# MCUSTM32F4ZGT6.net
KiCad netlist of a schematic drawn in Altium Designer
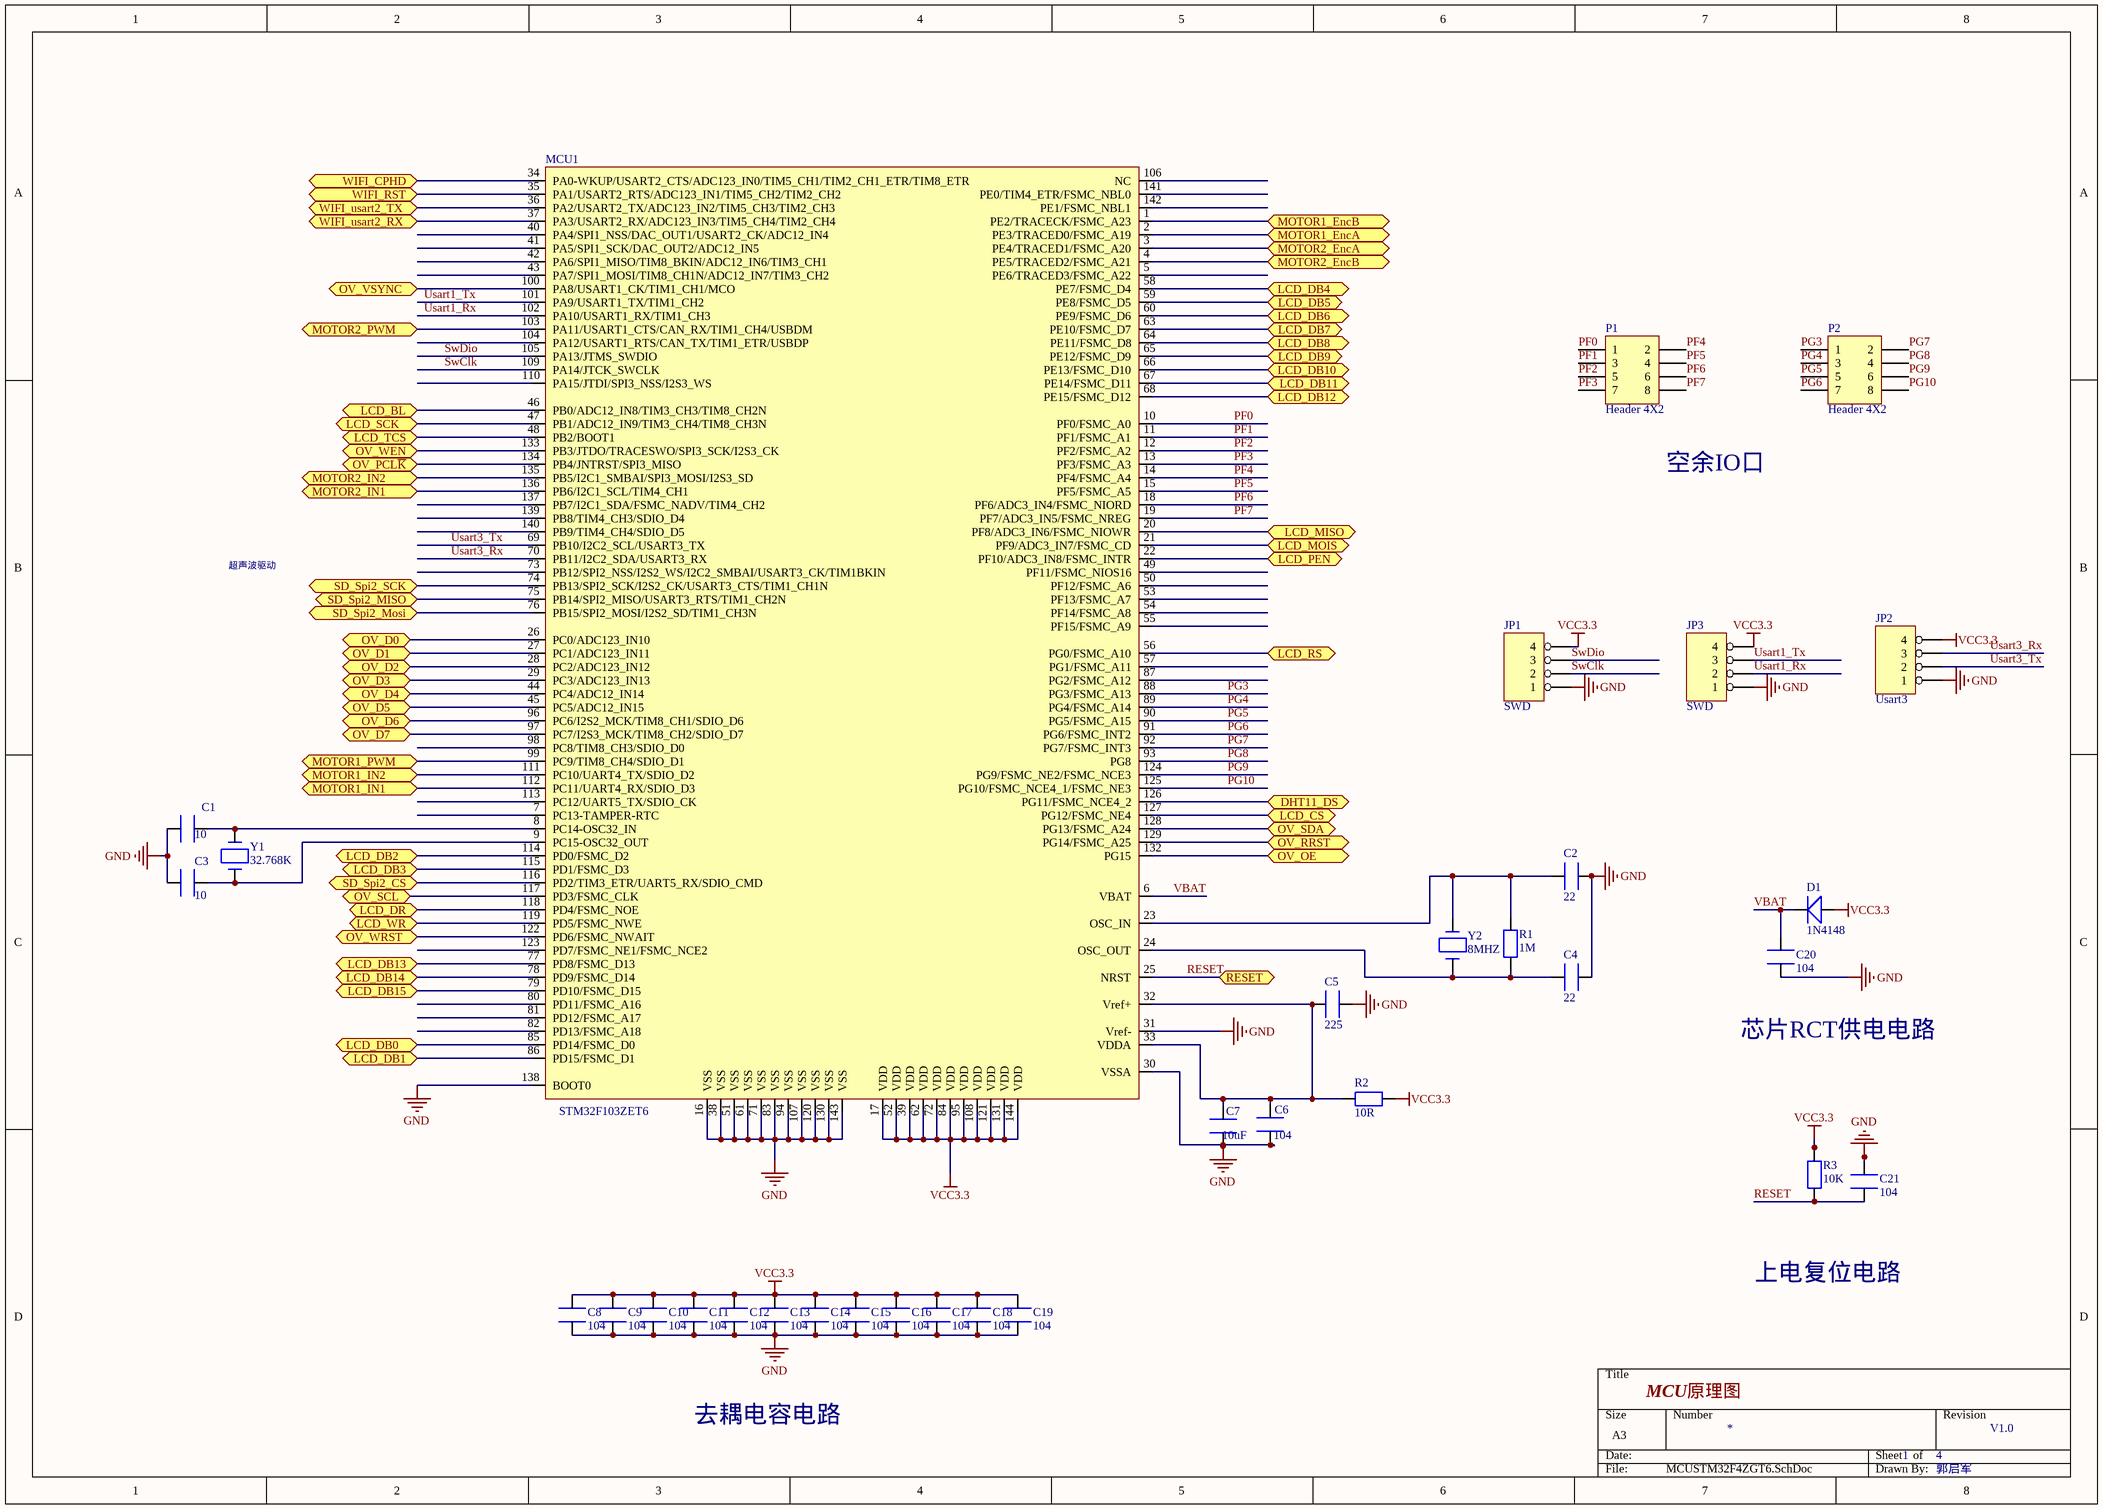
[diagram p0: MCUSTM32F4ZGT6.SchDoc]

(export (version "E")
  (design (tool "Eeschema 10.0.6"))
  (components
    (comp (ref "C1")
      (value "10")
      (footprint "0805-bottom layer")
      (description "电容")
      (libsource (lib "Baymax") (part "10"))
    )
    (comp (ref "C2")
      (value "22")
      (footprint "0805-bottom layer")
      (description "电容")
      (libsource (lib "Baymax") (part "22"))
    )
    (comp (ref "C3")
      (value "10")
      (footprint "0805-bottom layer")
      (description "电容")
      (libsource (lib "Baymax") (part "10"))
    )
    (comp (ref "C4")
      (value "22")
      (footprint "0805-bottom layer")
      (description "电容")
      (libsource (lib "Baymax") (part "22"))
    )
    (comp (ref "C5")
      (value "225")
      (footprint "0805-bottom layer")
      (description "电容")
      (libsource (lib "Baymax") (part "225"))
    )
    (comp (ref "C6")
      (value "104")
      (footprint "0805-bottom layer")
      (description "电容")
      (libsource (lib "Baymax") (part "104"))
    )
    (comp (ref "C7")
      (value "10uF")
      (footprint "0805-bottom layer")
      (description "电容")
      (libsource (lib "Baymax") (part "10uF"))
    )
    (comp (ref "C8")
      (value "104")
      (footprint "0805-bottom layer")
      (description "电容")
      (libsource (lib "Baymax") (part "104"))
    )
    (comp (ref "C9")
      (value "104")
      (footprint "0805-bottom layer")
      (description "电容")
      (libsource (lib "Baymax") (part "104"))
    )
    (comp (ref "C10")
      (value "104")
      (footprint "0805-bottom layer")
      (description "电容")
      (libsource (lib "Baymax") (part "104"))
    )
    (comp (ref "C11")
      (value "104")
      (footprint "0805-bottom layer")
      (description "电容")
      (libsource (lib "Baymax") (part "104"))
    )
    (comp (ref "C12")
      (value "104")
      (footprint "0805-bottom layer")
      (description "电容")
      (libsource (lib "Baymax") (part "104"))
    )
    (comp (ref "C13")
      (value "104")
      (footprint "0805-bottom layer")
      (description "电容")
      (libsource (lib "Baymax") (part "104"))
    )
    (comp (ref "C14")
      (value "104")
      (footprint "0805-bottom layer")
      (description "电容")
      (libsource (lib "Baymax") (part "104"))
    )
    (comp (ref "C15")
      (value "104")
      (footprint "0805-bottom layer")
      (description "电容")
      (libsource (lib "Baymax") (part "104"))
    )
    (comp (ref "C16")
      (value "104")
      (footprint "0805-bottom layer")
      (description "电容")
      (libsource (lib "Baymax") (part "104"))
    )
    (comp (ref "C17")
      (value "104")
      (footprint "0805-bottom layer")
      (description "电容")
      (libsource (lib "Baymax") (part "104"))
    )
    (comp (ref "C18")
      (value "104")
      (footprint "0805-bottom layer")
      (description "电容")
      (libsource (lib "Baymax") (part "104"))
    )
    (comp (ref "C19")
      (value "104")
      (footprint "0805-bottom layer")
      (description "电容")
      (libsource (lib "Baymax") (part "104"))
    )
    (comp (ref "C20")
      (value "104")
      (footprint "0805-bottom layer")
      (description "电容")
      (libsource (lib "Baymax") (part "104"))
    )
    (comp (ref "C21")
      (value "104")
      (footprint "0805-bottom layer")
      (description "电容")
      (libsource (lib "Baymax") (part "104"))
    )
    (comp (ref "D1")
      (value "1N4148")
      (footprint "DIODE_SOP")
      (description "限流二极管")
      (libsource (lib "Baymax") (part "1N4148"))
    )
    (comp (ref "JP1")
      (value "SWD")
      (footprint "HDR1X4")
      (libsource (lib "Connector Class") (part "HEADER 4"))
    )
    (comp (ref "JP2")
      (value "Usart3")
      (footprint "HDR1X4")
      (libsource (lib "Connector Class") (part "HEADER 4"))
    )
    (comp (ref "JP3") (value "SWD") (footprint "HDR1X4") (libsource (lib "BAYMAX_") (part "HEADER 4")))
    (comp (ref "MCU1")
      (value "STM32F103ZET6")
      (footprint "LQFP144")
      (libsource (lib "Baymax") (part "STM32F103ZET6"))
    )
    (comp (ref "P1")
      (value "Header 4X2")
      (footprint "HDR2X4")
      (description "Header, 4-Pin, Dual row")
      (fields (field (name "PUBLISHER") "Altium Limited"))
      (libsource (lib "Miscellaneous Connectors") (part "Header 4X2"))
    )
    (comp (ref "P2")
      (value "Header 4X2")
      (footprint "HDR2X4")
      (description "Header, 4-Pin, Dual row")
      (fields (field (name "PUBLISHER") "Altium Limited"))
      (libsource (lib "Miscellaneous Connectors") (part "Header 4X2"))
    )
    (comp (ref "R1")
      (value "1M")
      (footprint "0805-bottom layer")
      (description "电阻")
      (libsource (lib "Baymax") (part "1M"))
    )
    (comp (ref "R2")
      (value "10R")
      (footprint "0805-bottom layer")
      (description "电阻")
      (libsource (lib "Baymax") (part "10R"))
    )
    (comp (ref "R3")
      (value "10K")
      (footprint "0805-bottom layer")
      (description "电阻")
      (libsource (lib "Baymax") (part "10K"))
    )
    (comp (ref "Y1")
      (value "32.768K")
      (footprint "XTAL32")
      (description "晶振")
      (libsource (lib "Baymax") (part "32.768K"))
    )
    (comp (ref "Y2")
      (value "8MHZ")
      (footprint "XTAL_US")
      (description "晶振")
      (libsource (lib "Baymax") (part "8MHZ"))
    )
  )
  (nets
    (net (code "1") (name "/DHT11_DS") (class "Default")
      (node (ref "MCU1") (pin "126") (pinfunction "PG11/FSMC_NCE4_2_126") (pintype "passive"))
    )
    (net (code "2") (name "/LCD_BL") (class "Default")
      (node (ref "MCU1") (pin "46") (pinfunction "PB0/ADC12_IN8/TIM3_CH3/TIM8_CH2N_46") (pintype "passive"))
    )
    (net (code "3") (name "/LCD_CS") (class "Default")
      (node (ref "MCU1") (pin "127") (pinfunction "PG12/FSMC_NE4_127") (pintype "passive"))
    )
    (net (code "4") (name "/LCD_DB0") (class "Default")
      (node (ref "MCU1") (pin "85") (pinfunction "PD14/FSMC_D0_85") (pintype "passive"))
    )
    (net (code "5") (name "/LCD_DB1") (class "Default")
      (node (ref "MCU1") (pin "86") (pinfunction "PD15/FSMC_D1_86") (pintype "passive"))
    )
    (net (code "6") (name "/LCD_DB2") (class "Default")
      (node (ref "MCU1") (pin "114") (pinfunction "PD0/FSMC_D2_114") (pintype "passive"))
    )
    (net (code "7") (name "/LCD_DB3") (class "Default")
      (node (ref "MCU1") (pin "115") (pinfunction "PD1/FSMC_D3_115") (pintype "passive"))
    )
    (net (code "8") (name "/LCD_DB4") (class "Default")
      (node (ref "MCU1") (pin "58") (pinfunction "PE7/FSMC_D4_58") (pintype "passive"))
    )
    (net (code "9") (name "/LCD_DB5") (class "Default")
      (node (ref "MCU1") (pin "59") (pinfunction "PE8/FSMC_D5_59") (pintype "passive"))
    )
    (net (code "10") (name "/LCD_DB6") (class "Default")
      (node (ref "MCU1") (pin "60") (pinfunction "PE9/FSMC_D6_60") (pintype "passive"))
    )
    (net (code "11") (name "/LCD_DB7") (class "Default")
      (node (ref "MCU1") (pin "63") (pinfunction "PE10/FSMC_D7_63") (pintype "passive"))
    )
    (net (code "12") (name "/LCD_DB8") (class "Default")
      (node (ref "MCU1") (pin "64") (pinfunction "PE11/FSMC_D8_64") (pintype "passive"))
    )
    (net (code "13") (name "/LCD_DB9") (class "Default")
      (node (ref "MCU1") (pin "65") (pinfunction "PE12/FSMC_D9_65") (pintype "passive"))
    )
    (net (code "14") (name "/LCD_DB10") (class "Default")
      (node (ref "MCU1") (pin "66") (pinfunction "PE13/FSMC_D10_66") (pintype "passive"))
    )
    (net (code "15") (name "/LCD_DB11") (class "Default")
      (node (ref "MCU1") (pin "67") (pinfunction "PE14/FSMC_D11_67") (pintype "passive"))
    )
    (net (code "16") (name "/LCD_DB12") (class "Default")
      (node (ref "MCU1") (pin "68") (pinfunction "PE15/FSMC_D12_68") (pintype "passive"))
    )
    (net (code "17") (name "/LCD_DB13") (class "Default")
      (node (ref "MCU1") (pin "77") (pinfunction "PD8/FSMC_D13_77") (pintype "passive"))
    )
    (net (code "18") (name "/LCD_DB14") (class "Default")
      (node (ref "MCU1") (pin "78") (pinfunction "PD9/FSMC_D14_78") (pintype "passive"))
    )
    (net (code "19") (name "/LCD_DB15") (class "Default")
      (node (ref "MCU1") (pin "79") (pinfunction "PD10/FSMC_D15_79") (pintype "passive"))
    )
    (net (code "20") (name "/LCD_DR") (class "Default")
      (node (ref "MCU1") (pin "118") (pinfunction "PD4/FSMC_NOE_118") (pintype "passive"))
    )
    (net (code "21") (name "/LCD_MISO") (class "Default")
      (node (ref "MCU1") (pin "20") (pinfunction "PF8/ADC3_IN6/FSMC_NIOWR_20") (pintype "passive"))
    )
    (net (code "22") (name "/LCD_MOIS") (class "Default")
      (node (ref "MCU1") (pin "21") (pinfunction "PF9/ADC3_IN7/FSMC_CD_21") (pintype "passive"))
    )
    (net (code "23") (name "/LCD_PEN") (class "Default")
      (node (ref "MCU1") (pin "22") (pinfunction "PF10/ADC3_IN8/FSMC_INTR_22") (pintype "passive"))
    )
    (net (code "24") (name "/LCD_RS") (class "Default")
      (node (ref "MCU1") (pin "56") (pinfunction "PG0/FSMC_A10_56") (pintype "passive"))
    )
    (net (code "25") (name "/LCD_SCK") (class "Default")
      (node (ref "MCU1") (pin "47") (pinfunction "PB1/ADC12_IN9/TIM3_CH4/TIM8_CH3N_47") (pintype "passive"))
    )
    (net (code "26") (name "/LCD_TCS") (class "Default")
      (node (ref "MCU1") (pin "48") (pinfunction "PB2/BOOT1_48") (pintype "passive"))
    )
    (net (code "27") (name "/LCD_WR") (class "Default")
      (node (ref "MCU1") (pin "119") (pinfunction "PD5/FSMC_NWE_119") (pintype "passive"))
    )
    (net (code "28") (name "/MOTOR1_EncA") (class "Default")
      (node (ref "MCU1") (pin "2") (pinfunction "PE3/TRACED0/FSMC_A19_2") (pintype "passive"))
    )
    (net (code "29") (name "/MOTOR1_EncB") (class "Default")
      (node (ref "MCU1") (pin "1") (pinfunction "PE2/TRACECK/FSMC_A23_1") (pintype "passive"))
    )
    (net (code "30") (name "/MOTOR1_IN1") (class "Default")
      (node (ref "MCU1") (pin "112") (pinfunction "PC11/UART4_RX/SDIO_D3_112") (pintype "passive"))
    )
    (net (code "31") (name "/MOTOR1_IN2") (class "Default")
      (node (ref "MCU1") (pin "111") (pinfunction "PC10/UART4_TX/SDIO_D2_111") (pintype "passive"))
    )
    (net (code "32") (name "/MOTOR1_PWM") (class "Default")
      (node (ref "MCU1") (pin "99") (pinfunction "PC9/TIM8_CH4/SDIO_D1_99") (pintype "passive"))
    )
    (net (code "33") (name "/MOTOR2_EncA") (class "Default")
      (node (ref "MCU1") (pin "3") (pinfunction "PE4/TRACED1/FSMC_A20_3") (pintype "passive"))
    )
    (net (code "34") (name "/MOTOR2_EncB") (class "Default")
      (node (ref "MCU1") (pin "4") (pinfunction "PE5/TRACED2/FSMC_A21_4") (pintype "passive"))
    )
    (net (code "35") (name "/MOTOR2_IN1") (class "Default")
      (node (ref "MCU1") (pin "136") (pinfunction "PB6/I2C1_SCL/TIM4_CH1_136") (pintype "passive"))
    )
    (net (code "36") (name "/MOTOR2_IN2") (class "Default")
      (node (ref "MCU1") (pin "135") (pinfunction "PB5/I2C1_SMBAI/SPI3_MOSI/I2S3_SD_135") (pintype "passive"))
    )
    (net (code "37") (name "/MOTOR2_PWM") (class "Default")
      (node (ref "MCU1") (pin "103") (pinfunction "PA11/USART1_CTS/CAN_RX/TIM1_CH4/USBDM_103") (pintype "passive"))
    )
    (net (code "38") (name "/OV_D0") (class "Default")
      (node (ref "MCU1") (pin "26") (pinfunction "PC0/ADC123_IN10_26") (pintype "passive"))
    )
    (net (code "39") (name "/OV_D1") (class "Default")
      (node (ref "MCU1") (pin "27") (pinfunction "PC1/ADC123_IN11_27") (pintype "passive"))
    )
    (net (code "40") (name "/OV_D2") (class "Default")
      (node (ref "MCU1") (pin "28") (pinfunction "PC2/ADC123_IN12_28") (pintype "passive"))
    )
    (net (code "41") (name "/OV_D3") (class "Default")
      (node (ref "MCU1") (pin "29") (pinfunction "PC3/ADC123_IN13_29") (pintype "passive"))
    )
    (net (code "42") (name "/OV_D4") (class "Default")
      (node (ref "MCU1") (pin "44") (pinfunction "PC4/ADC12_IN14_44") (pintype "passive"))
    )
    (net (code "43") (name "/OV_D5") (class "Default")
      (node (ref "MCU1") (pin "45") (pinfunction "PC5/ADC12_IN15_45") (pintype "passive"))
    )
    (net (code "44") (name "/OV_D6") (class "Default")
      (node (ref "MCU1") (pin "96") (pinfunction "PC6/I2S2_MCK/TIM8_CH1/SDIO_D6_96") (pintype "passive"))
    )
    (net (code "45") (name "/OV_D7") (class "Default")
      (node (ref "MCU1") (pin "97") (pinfunction "PC7/I2S3_MCK/TIM8_CH2/SDIO_D7_97") (pintype "passive"))
    )
    (net (code "46") (name "/OV_OE") (class "Default")
      (node (ref "MCU1") (pin "132") (pinfunction "PG15_132") (pintype "passive"))
    )
    (net (code "47") (name "/OV_PCL~{K}") (class "Default")
      (node (ref "MCU1") (pin "134") (pinfunction "PB4/JNTRST/SPI3_MISO_134") (pintype "passive"))
    )
    (net (code "48") (name "/OV_RRST") (class "Default")
      (node (ref "MCU1") (pin "129") (pinfunction "PG14/FSMC_A25_129") (pintype "passive"))
    )
    (net (code "49") (name "/OV_SCL") (class "Default")
      (node (ref "MCU1") (pin "117") (pinfunction "PD3/FSMC_CLK_117") (pintype "passive"))
    )
    (net (code "50") (name "/OV_SDA") (class "Default")
      (node (ref "MCU1") (pin "128") (pinfunction "PG13/FSMC_A24_128") (pintype "passive"))
    )
    (net (code "51") (name "/OV_VSYNC") (class "Default")
      (node (ref "MCU1") (pin "100") (pinfunction "PA8/USART1_CK/TIM1_CH1/MCO_100") (pintype "passive"))
    )
    (net (code "52") (name "/OV_WEN") (class "Default")
      (node (ref "MCU1") (pin "133") (pinfunction "PB3/JTDO/TRACESWO/SPI3_SCK/I2S3_CK_133") (pintype "passive"))
    )
    (net (code "53") (name "/OV_WRST") (class "Default")
      (node (ref "MCU1") (pin "122") (pinfunction "PD6/FSMC_NWAIT_122") (pintype "passive"))
    )
    (net (code "54") (name "/PF0") (class "Default")
      (node (ref "MCU1") (pin "10") (pinfunction "PF0/FSMC_A0_10") (pintype "passive"))
      (node (ref "P1") (pin "1") (pinfunction "1_1") (pintype "passive"))
    )
    (net (code "55") (name "/PF1") (class "Default")
      (node (ref "MCU1") (pin "11") (pinfunction "PF1/FSMC_A1_11") (pintype "passive"))
      (node (ref "P1") (pin "3") (pinfunction "3_3") (pintype "passive"))
    )
    (net (code "56") (name "/PF2") (class "Default")
      (node (ref "MCU1") (pin "12") (pinfunction "PF2/FSMC_A2_12") (pintype "passive"))
      (node (ref "P1") (pin "5") (pinfunction "5_5") (pintype "passive"))
    )
    (net (code "57") (name "/PF3") (class "Default")
      (node (ref "MCU1") (pin "13") (pinfunction "PF3/FSMC_A3_13") (pintype "passive"))
      (node (ref "P1") (pin "7") (pinfunction "7_7") (pintype "passive"))
    )
    (net (code "58") (name "/PF4") (class "Default")
      (node (ref "MCU1") (pin "14") (pinfunction "PF4/FSMC_A4_14") (pintype "passive"))
      (node (ref "P1") (pin "2") (pinfunction "2_2") (pintype "passive"))
    )
    (net (code "59") (name "/PF5") (class "Default")
      (node (ref "MCU1") (pin "15") (pinfunction "PF5/FSMC_A5_15") (pintype "passive"))
      (node (ref "P1") (pin "4") (pinfunction "4_4") (pintype "passive"))
    )
    (net (code "60") (name "/PF6") (class "Default")
      (node (ref "MCU1") (pin "18") (pinfunction "PF6/ADC3_IN4/FSMC_NIORD_18") (pintype "passive"))
      (node (ref "P1") (pin "6") (pinfunction "6_6") (pintype "passive"))
    )
    (net (code "61") (name "/PF7") (class "Default")
      (node (ref "MCU1") (pin "19") (pinfunction "PF7/ADC3_IN5/FSMC_NREG_19") (pintype "passive"))
      (node (ref "P1") (pin "8") (pinfunction "8_8") (pintype "passive"))
    )
    (net (code "62") (name "/PG3") (class "Default")
      (node (ref "MCU1") (pin "88") (pinfunction "PG3/FSMC_A13_88") (pintype "passive"))
      (node (ref "P2") (pin "1") (pinfunction "1_1") (pintype "passive"))
    )
    (net (code "63") (name "/PG4") (class "Default")
      (node (ref "MCU1") (pin "89") (pinfunction "PG4/FSMC_A14_89") (pintype "passive"))
      (node (ref "P2") (pin "3") (pinfunction "3_3") (pintype "passive"))
    )
    (net (code "64") (name "/PG5") (class "Default")
      (node (ref "MCU1") (pin "90") (pinfunction "PG5/FSMC_A15_90") (pintype "passive"))
      (node (ref "P2") (pin "5") (pinfunction "5_5") (pintype "passive"))
    )
    (net (code "65") (name "/PG6") (class "Default")
      (node (ref "MCU1") (pin "91") (pinfunction "PG6/FSMC_INT2_91") (pintype "passive"))
      (node (ref "P2") (pin "7") (pinfunction "7_7") (pintype "passive"))
    )
    (net (code "66") (name "/PG7") (class "Default")
      (node (ref "MCU1") (pin "92") (pinfunction "PG7/FSMC_INT3_92") (pintype "passive"))
      (node (ref "P2") (pin "2") (pinfunction "2_2") (pintype "passive"))
    )
    (net (code "67") (name "/PG8") (class "Default")
      (node (ref "MCU1") (pin "93") (pinfunction "PG8_93") (pintype "passive"))
      (node (ref "P2") (pin "4") (pinfunction "4_4") (pintype "passive"))
    )
    (net (code "68") (name "/PG9") (class "Default")
      (node (ref "MCU1") (pin "124") (pinfunction "PG9/FSMC_NE2/FSMC_NCE3_124") (pintype "passive"))
      (node (ref "P2") (pin "6") (pinfunction "6_6") (pintype "passive"))
    )
    (net (code "69") (name "/PG10") (class "Default")
      (node (ref "MCU1") (pin "125") (pinfunction "PG10/FSMC_NCE4_1/FSMC_NE3_125") (pintype "passive"))
      (node (ref "P2") (pin "8") (pinfunction "8_8") (pintype "passive"))
    )
    (net (code "70") (name "/RESET") (class "Default")
      (node (ref "C21") (pin "2") (pintype "passive"))
      (node (ref "MCU1") (pin "25") (pinfunction "NRST_25") (pintype "passive"))
      (node (ref "R3") (pin "1") (pintype "passive"))
    )
    (net (code "71") (name "/SD_Spi2_CS") (class "Default")
      (node (ref "MCU1") (pin "116") (pinfunction "PD2/TIM3_ETR/UART5_RX/SDIO_CMD_116") (pintype "passive"))
    )
    (net (code "72") (name "/SD_Spi2_MISO") (class "Default")
      (node (ref "MCU1") (pin "75") (pinfunction "PB14/SPI2_MISO/USART3_RTS/TIM1_CH2N_75") (pintype "passive"))
    )
    (net (code "73") (name "/SD_Spi2_Mosi") (class "Default")
      (node (ref "MCU1") (pin "76") (pinfunction "PB15/SPI2_MOSI/I2S2_SD/TIM1_CH3N_76") (pintype "passive"))
    )
    (net (code "74") (name "/SD_Spi2_SCK") (class "Default")
      (node (ref "MCU1") (pin "74") (pinfunction "PB13/SPI2_SCK/I2S2_CK/USART3_CTS/TIM1_CH1N_74") (pintype "passive"))
    )
    (net (code "75") (name "/SwClk") (class "Default")
      (node (ref "JP1") (pin "2") (pinfunction "2_2") (pintype "passive"))
      (node (ref "MCU1") (pin "109") (pinfunction "PA14/JTCK_SWCLK_109") (pintype "passive"))
    )
    (net (code "76") (name "/SwDio") (class "Default")
      (node (ref "JP1") (pin "3") (pinfunction "3_3") (pintype "passive"))
      (node (ref "MCU1") (pin "105") (pinfunction "PA13/JTMS_SWDIO_105") (pintype "passive"))
    )
    (net (code "77") (name "/Usart1_Rx") (class "Default")
      (node (ref "JP3") (pin "2") (pinfunction "2_2") (pintype "passive"))
      (node (ref "MCU1") (pin "102") (pinfunction "PA10/USART1_RX/TIM1_CH3_102") (pintype "passive"))
    )
    (net (code "78") (name "/Usart1_Tx") (class "Default")
      (node (ref "JP3") (pin "3") (pinfunction "3_3") (pintype "passive"))
      (node (ref "MCU1") (pin "101") (pinfunction "PA9/USART1_TX/TIM1_CH2_101") (pintype "passive"))
    )
    (net (code "79") (name "/Usart3_Rx") (class "Default")
      (node (ref "JP2") (pin "3") (pinfunction "3_3") (pintype "passive"))
      (node (ref "MCU1") (pin "70") (pinfunction "PB11/I2C2_SDA/USART3_RX_70") (pintype "passive"))
    )
    (net (code "80") (name "/Usart3_Tx") (class "Default")
      (node (ref "JP2") (pin "2") (pinfunction "2_2") (pintype "passive"))
      (node (ref "MCU1") (pin "69") (pinfunction "PB10/I2C2_SCL/USART3_TX_69") (pintype "passive"))
    )
    (net (code "81") (name "/VBAT") (class "Default")
      (node (ref "C20") (pin "2") (pintype "passive"))
      (node (ref "D1") (pin "2") (pintype "passive"))
      (node (ref "MCU1") (pin "6") (pinfunction "VBAT_6") (pintype "passive"))
    )
    (net (code "82") (name "/WIFI_CPHD") (class "Default")
      (node (ref "MCU1") (pin "34") (pinfunction "PA0-WKUP/USART2_CTS/ADC123_IN0/TIM5_CH1/TIM2_CH1_ETR/TIM8_ETR_34") (pintype "passive"))
    )
    (net (code "83") (name "/WIFI_RST") (class "Default")
      (node (ref "MCU1") (pin "35") (pinfunction "PA1/USART2_RTS/ADC123_IN1/TIM5_CH2/TIM2_CH2_35") (pintype "passive"))
    )
    (net (code "84") (name "/WIFI_usart2_RX") (class "Default")
      (node (ref "MCU1") (pin "37") (pinfunction "PA3/USART2_RX/ADC123_IN3/TIM5_CH4/TIM2_CH4_37") (pintype "passive"))
    )
    (net (code "85") (name "/WIFI_usart2_TX") (class "Default")
      (node (ref "MCU1") (pin "36") (pinfunction "PA2/USART2_TX/ADC123_IN2/TIM5_CH3/TIM2_CH3_36") (pintype "passive"))
    )
    (net (code "86") (name "GND") (class "Default")
      (node (ref "C1") (pin "2") (pintype "passive"))
      (node (ref "C10") (pin "2") (pintype "passive"))
      (node (ref "C11") (pin "2") (pintype "passive"))
      (node (ref "C12") (pin "2") (pintype "passive"))
      (node (ref "C13") (pin "2") (pintype "passive"))
      (node (ref "C14") (pin "2") (pintype "passive"))
      (node (ref "C15") (pin "2") (pintype "passive"))
      (node (ref "C16") (pin "2") (pintype "passive"))
      (node (ref "C17") (pin "2") (pintype "passive"))
      (node (ref "C18") (pin "2") (pintype "passive"))
      (node (ref "C19") (pin "2") (pintype "passive"))
      (node (ref "C2") (pin "1") (pintype "passive"))
      (node (ref "C20") (pin "1") (pintype "passive"))
      (node (ref "C21") (pin "1") (pintype "passive"))
      (node (ref "C3") (pin "1") (pintype "passive"))
      (node (ref "C4") (pin "1") (pintype "passive"))
      (node (ref "C5") (pin "1") (pintype "passive"))
      (node (ref "C6") (pin "2") (pintype "passive"))
      (node (ref "C7") (pin "2") (pintype "passive"))
      (node (ref "C8") (pin "2") (pintype "passive"))
      (node (ref "C9") (pin "2") (pintype "passive"))
      (node (ref "JP1") (pin "1") (pinfunction "1_1") (pintype "passive"))
      (node (ref "JP2") (pin "1") (pinfunction "1_1") (pintype "passive"))
      (node (ref "JP3") (pin "1") (pinfunction "1_1") (pintype "passive"))
      (node (ref "MCU1") (pin "107") (pinfunction "VSS_107") (pintype "passive"))
      (node (ref "MCU1") (pin "120") (pinfunction "VSS_120") (pintype "passive"))
      (node (ref "MCU1") (pin "130") (pinfunction "VSS_130") (pintype "passive"))
      (node (ref "MCU1") (pin "138") (pinfunction "BOOT0_138") (pintype "passive"))
      (node (ref "MCU1") (pin "143") (pinfunction "VSS_143") (pintype "passive"))
      (node (ref "MCU1") (pin "16") (pinfunction "VSS_16") (pintype "passive"))
      (node (ref "MCU1") (pin "30") (pinfunction "VSSA_30") (pintype "passive"))
      (node (ref "MCU1") (pin "31") (pinfunction "Vref-_31") (pintype "passive"))
      (node (ref "MCU1") (pin "38") (pinfunction "VSS_38") (pintype "passive"))
      (node (ref "MCU1") (pin "51") (pinfunction "VSS_51") (pintype "passive"))
      (node (ref "MCU1") (pin "61") (pinfunction "VSS_61") (pintype "passive"))
      (node (ref "MCU1") (pin "71") (pinfunction "VSS_71") (pintype "passive"))
      (node (ref "MCU1") (pin "83") (pinfunction "VSS_83") (pintype "passive"))
      (node (ref "MCU1") (pin "94") (pinfunction "VSS_94") (pintype "passive"))
    )
    (net (code "87") (name "Net-(MCU1-OSC_IN)") (class "Default")
      (node (ref "C2") (pin "2") (pintype "passive"))
      (node (ref "MCU1") (pin "23") (pinfunction "OSC_IN_23") (pintype "passive"))
      (node (ref "R1") (pin "2") (pintype "passive"))
      (node (ref "Y2") (pin "1") (pintype "passive"))
    )
    (net (code "88") (name "Net-(MCU1-OSC_OUT)") (class "Default")
      (node (ref "C4") (pin "2") (pintype "passive"))
      (node (ref "MCU1") (pin "24") (pinfunction "OSC_OUT_24") (pintype "passive"))
      (node (ref "R1") (pin "1") (pintype "passive"))
      (node (ref "Y2") (pin "2") (pintype "passive"))
    )
    (net (code "89") (name "Net-(MCU1-PC14-OSC32_IN)") (class "Default")
      (node (ref "C1") (pin "1") (pintype "passive"))
      (node (ref "MCU1") (pin "8") (pinfunction "PC14-OSC32_IN_8") (pintype "passive"))
      (node (ref "Y1") (pin "2") (pintype "passive"))
    )
    (net (code "90") (name "Net-(MCU1-PC15-OSC32_OUT)") (class "Default")
      (node (ref "C3") (pin "2") (pintype "passive"))
      (node (ref "MCU1") (pin "9") (pinfunction "PC15-OSC32_OUT_9") (pintype "passive"))
      (node (ref "Y1") (pin "1") (pintype "passive"))
    )
    (net (code "91") (name "Net-(MCU1-VDDA)") (class "Default")
      (node (ref "C5") (pin "2") (pintype "passive"))
      (node (ref "C6") (pin "1") (pintype "passive"))
      (node (ref "C7") (pin "1") (pintype "passive"))
      (node (ref "MCU1") (pin "32") (pinfunction "Vref+_32") (pintype "passive"))
      (node (ref "MCU1") (pin "33") (pinfunction "VDDA_33") (pintype "passive"))
      (node (ref "R2") (pin "1") (pintype "passive"))
    )
    (net (code "92") (name "VCC3.3") (class "Default")
      (node (ref "C10") (pin "1") (pintype "passive"))
      (node (ref "C11") (pin "1") (pintype "passive"))
      (node (ref "C12") (pin "1") (pintype "passive"))
      (node (ref "C13") (pin "1") (pintype "passive"))
      (node (ref "C14") (pin "1") (pintype "passive"))
      (node (ref "C15") (pin "1") (pintype "passive"))
      (node (ref "C16") (pin "1") (pintype "passive"))
      (node (ref "C17") (pin "1") (pintype "passive"))
      (node (ref "C18") (pin "1") (pintype "passive"))
      (node (ref "C19") (pin "1") (pintype "passive"))
      (node (ref "C8") (pin "1") (pintype "passive"))
      (node (ref "C9") (pin "1") (pintype "passive"))
      (node (ref "D1") (pin "1") (pintype "passive"))
      (node (ref "JP1") (pin "4") (pinfunction "4_4") (pintype "passive"))
      (node (ref "JP2") (pin "4") (pinfunction "4_4") (pintype "passive"))
      (node (ref "JP3") (pin "4") (pinfunction "4_4") (pintype "passive"))
      (node (ref "MCU1") (pin "108") (pinfunction "VDD_108") (pintype "passive"))
      (node (ref "MCU1") (pin "121") (pinfunction "VDD_121") (pintype "passive"))
      (node (ref "MCU1") (pin "131") (pinfunction "VDD_131") (pintype "passive"))
      (node (ref "MCU1") (pin "144") (pinfunction "VDD_144") (pintype "passive"))
      (node (ref "MCU1") (pin "17") (pinfunction "VDD_17") (pintype "passive"))
      (node (ref "MCU1") (pin "39") (pinfunction "VDD_39") (pintype "passive"))
      (node (ref "MCU1") (pin "52") (pinfunction "VDD_52") (pintype "passive"))
      (node (ref "MCU1") (pin "62") (pinfunction "VDD_62") (pintype "passive"))
      (node (ref "MCU1") (pin "72") (pinfunction "VDD_72") (pintype "passive"))
      (node (ref "MCU1") (pin "84") (pinfunction "VDD_84") (pintype "passive"))
      (node (ref "MCU1") (pin "95") (pinfunction "VDD_95") (pintype "passive"))
      (node (ref "R2") (pin "2") (pintype "passive"))
      (node (ref "R3") (pin "2") (pintype "passive"))
    )
    (net (code "93") (name "unconnected-(MCU1-NC-Pad106)") (class "Default")
      (node (ref "MCU1") (pin "106") (pinfunction "NC_106") (pintype "passive"))
    )
    (net (code "94") (name "unconnected-(MCU1-PA4{slash}SPI1_NSS{slash}DAC_OUT1{slash}USART2_CK{slash}ADC12_IN4-Pad40)") (class "Default")
      (node (ref "MCU1") (pin "40") (pinfunction "PA4/SPI1_NSS/DAC_OUT1/USART2_CK/ADC12_IN4_40") (pintype "passive"))
    )
    (net (code "95") (name "unconnected-(MCU1-PA5{slash}SPI1_SCK{slash}DAC_OUT2{slash}ADC12_IN5-Pad41)") (class "Default")
      (node (ref "MCU1") (pin "41") (pinfunction "PA5/SPI1_SCK/DAC_OUT2/ADC12_IN5_41") (pintype "passive"))
    )
    (net (code "96") (name "unconnected-(MCU1-PA6{slash}SPI1_MISO{slash}TIM8_BKIN{slash}ADC12_IN6{slash}TIM3_CH1-Pad42)") (class "Default")
      (node (ref "MCU1") (pin "42") (pinfunction "PA6/SPI1_MISO/TIM8_BKIN/ADC12_IN6/TIM3_CH1_42") (pintype "passive"))
    )
    (net (code "97") (name "unconnected-(MCU1-PA7{slash}SPI1_MOSI{slash}TIM8_CH1N{slash}ADC12_IN7{slash}TIM3_CH2-Pad43)") (class "Default")
      (node (ref "MCU1") (pin "43") (pinfunction "PA7/SPI1_MOSI/TIM8_CH1N/ADC12_IN7/TIM3_CH2_43") (pintype "passive"))
    )
    (net (code "98") (name "unconnected-(MCU1-PA12{slash}USART1_RTS{slash}CAN_TX{slash}TIM1_ETR{slash}USBDP-Pad104)") (class "Default")
      (node (ref "MCU1") (pin "104") (pinfunction "PA12/USART1_RTS/CAN_TX/TIM1_ETR/USBDP_104") (pintype "passive"))
    )
    (net (code "99") (name "unconnected-(MCU1-PA15{slash}JTDI{slash}SPI3_NSS{slash}I2S3_WS-Pad110)") (class "Default")
      (node (ref "MCU1") (pin "110") (pinfunction "PA15/JTDI/SPI3_NSS/I2S3_WS_110") (pintype "passive"))
    )
    (net (code "100") (name "unconnected-(MCU1-PB7{slash}I2C1_SDA{slash}FSMC_NADV{slash}TIM4_CH2-Pad137)") (class "Default")
      (node (ref "MCU1") (pin "137") (pinfunction "PB7/I2C1_SDA/FSMC_NADV/TIM4_CH2_137") (pintype "passive"))
    )
    (net (code "101") (name "unconnected-(MCU1-PB8{slash}TIM4_CH3{slash}SDIO_D4-Pad139)") (class "Default")
      (node (ref "MCU1") (pin "139") (pinfunction "PB8/TIM4_CH3/SDIO_D4_139") (pintype "passive"))
    )
    (net (code "102") (name "unconnected-(MCU1-PB9{slash}TIM4_CH4{slash}SDIO_D5-Pad140)") (class "Default")
      (node (ref "MCU1") (pin "140") (pinfunction "PB9/TIM4_CH4/SDIO_D5_140") (pintype "passive"))
    )
    (net (code "103") (name "unconnected-(MCU1-PB12{slash}SPI2_NSS{slash}I2S2_WS{slash}I2C2_SMBAI{slash}USART3_CK{slash}TIM1BKIN-Pad73)") (class "Default")
      (node (ref "MCU1") (pin "73") (pinfunction "PB12/SPI2_NSS/I2S2_WS/I2C2_SMBAI/USART3_CK/TIM1BKIN_73") (pintype "passive"))
    )
    (net (code "104") (name "unconnected-(MCU1-PC8{slash}TIM8_CH3{slash}SDIO_D0-Pad98)") (class "Default")
      (node (ref "MCU1") (pin "98") (pinfunction "PC8/TIM8_CH3/SDIO_D0_98") (pintype "passive"))
    )
    (net (code "105") (name "unconnected-(MCU1-PC12{slash}UART5_TX{slash}SDIO_CK-Pad113)") (class "Default")
      (node (ref "MCU1") (pin "113") (pinfunction "PC12/UART5_TX/SDIO_CK_113") (pintype "passive"))
    )
    (net (code "106") (name "unconnected-(MCU1-PC13-TAMPER-RTC-Pad7)") (class "Default")
      (node (ref "MCU1") (pin "7") (pinfunction "PC13-TAMPER-RTC_7") (pintype "passive"))
    )
    (net (code "107") (name "unconnected-(MCU1-PD7{slash}FSMC_NE1{slash}FSMC_NCE2-Pad123)") (class "Default")
      (node (ref "MCU1") (pin "123") (pinfunction "PD7/FSMC_NE1/FSMC_NCE2_123") (pintype "passive"))
    )
    (net (code "108") (name "unconnected-(MCU1-PD11{slash}FSMC_A16-Pad80)") (class "Default")
      (node (ref "MCU1") (pin "80") (pinfunction "PD11/FSMC_A16_80") (pintype "passive"))
    )
    (net (code "109") (name "unconnected-(MCU1-PD12{slash}FSMC_A17-Pad81)") (class "Default")
      (node (ref "MCU1") (pin "81") (pinfunction "PD12/FSMC_A17_81") (pintype "passive"))
    )
    (net (code "110") (name "unconnected-(MCU1-PD13{slash}FSMC_A18-Pad82)") (class "Default")
      (node (ref "MCU1") (pin "82") (pinfunction "PD13/FSMC_A18_82") (pintype "passive"))
    )
    (net (code "111") (name "unconnected-(MCU1-PE0{slash}TIM4_ETR{slash}FSMC_NBL0-Pad141)") (class "Default")
      (node (ref "MCU1") (pin "141") (pinfunction "PE0/TIM4_ETR/FSMC_NBL0_141") (pintype "passive"))
    )
    (net (code "112") (name "unconnected-(MCU1-PE1{slash}FSMC_NBL1-Pad142)") (class "Default")
      (node (ref "MCU1") (pin "142") (pinfunction "PE1/FSMC_NBL1_142") (pintype "passive"))
    )
    (net (code "113") (name "unconnected-(MCU1-PE6{slash}TRACED3{slash}FSMC_A22-Pad5)") (class "Default")
      (node (ref "MCU1") (pin "5") (pinfunction "PE6/TRACED3/FSMC_A22_5") (pintype "passive"))
    )
    (net (code "114") (name "unconnected-(MCU1-PF11{slash}FSMC_NIOS16-Pad49)") (class "Default")
      (node (ref "MCU1") (pin "49") (pinfunction "PF11/FSMC_NIOS16_49") (pintype "passive"))
    )
    (net (code "115") (name "unconnected-(MCU1-PF12{slash}FSMC_A6-Pad50)") (class "Default")
      (node (ref "MCU1") (pin "50") (pinfunction "PF12/FSMC_A6_50") (pintype "passive"))
    )
    (net (code "116") (name "unconnected-(MCU1-PF13{slash}FSMC_A7-Pad53)") (class "Default")
      (node (ref "MCU1") (pin "53") (pinfunction "PF13/FSMC_A7_53") (pintype "passive"))
    )
    (net (code "117") (name "unconnected-(MCU1-PF14{slash}FSMC_A8-Pad54)") (class "Default")
      (node (ref "MCU1") (pin "54") (pinfunction "PF14/FSMC_A8_54") (pintype "passive"))
    )
    (net (code "118") (name "unconnected-(MCU1-PF15{slash}FSMC_A9-Pad55)") (class "Default")
      (node (ref "MCU1") (pin "55") (pinfunction "PF15/FSMC_A9_55") (pintype "passive"))
    )
    (net (code "119") (name "unconnected-(MCU1-PG1{slash}FSMC_A11-Pad57)") (class "Default")
      (node (ref "MCU1") (pin "57") (pinfunction "PG1/FSMC_A11_57") (pintype "passive"))
    )
    (net (code "120") (name "unconnected-(MCU1-PG2{slash}FSMC_A12-Pad87)") (class "Default")
      (node (ref "MCU1") (pin "87") (pinfunction "PG2/FSMC_A12_87") (pintype "passive"))
    )
  )
)
